# SyNetLEDv2.net
KiCad netlist of a schematic drawn in EAGLE
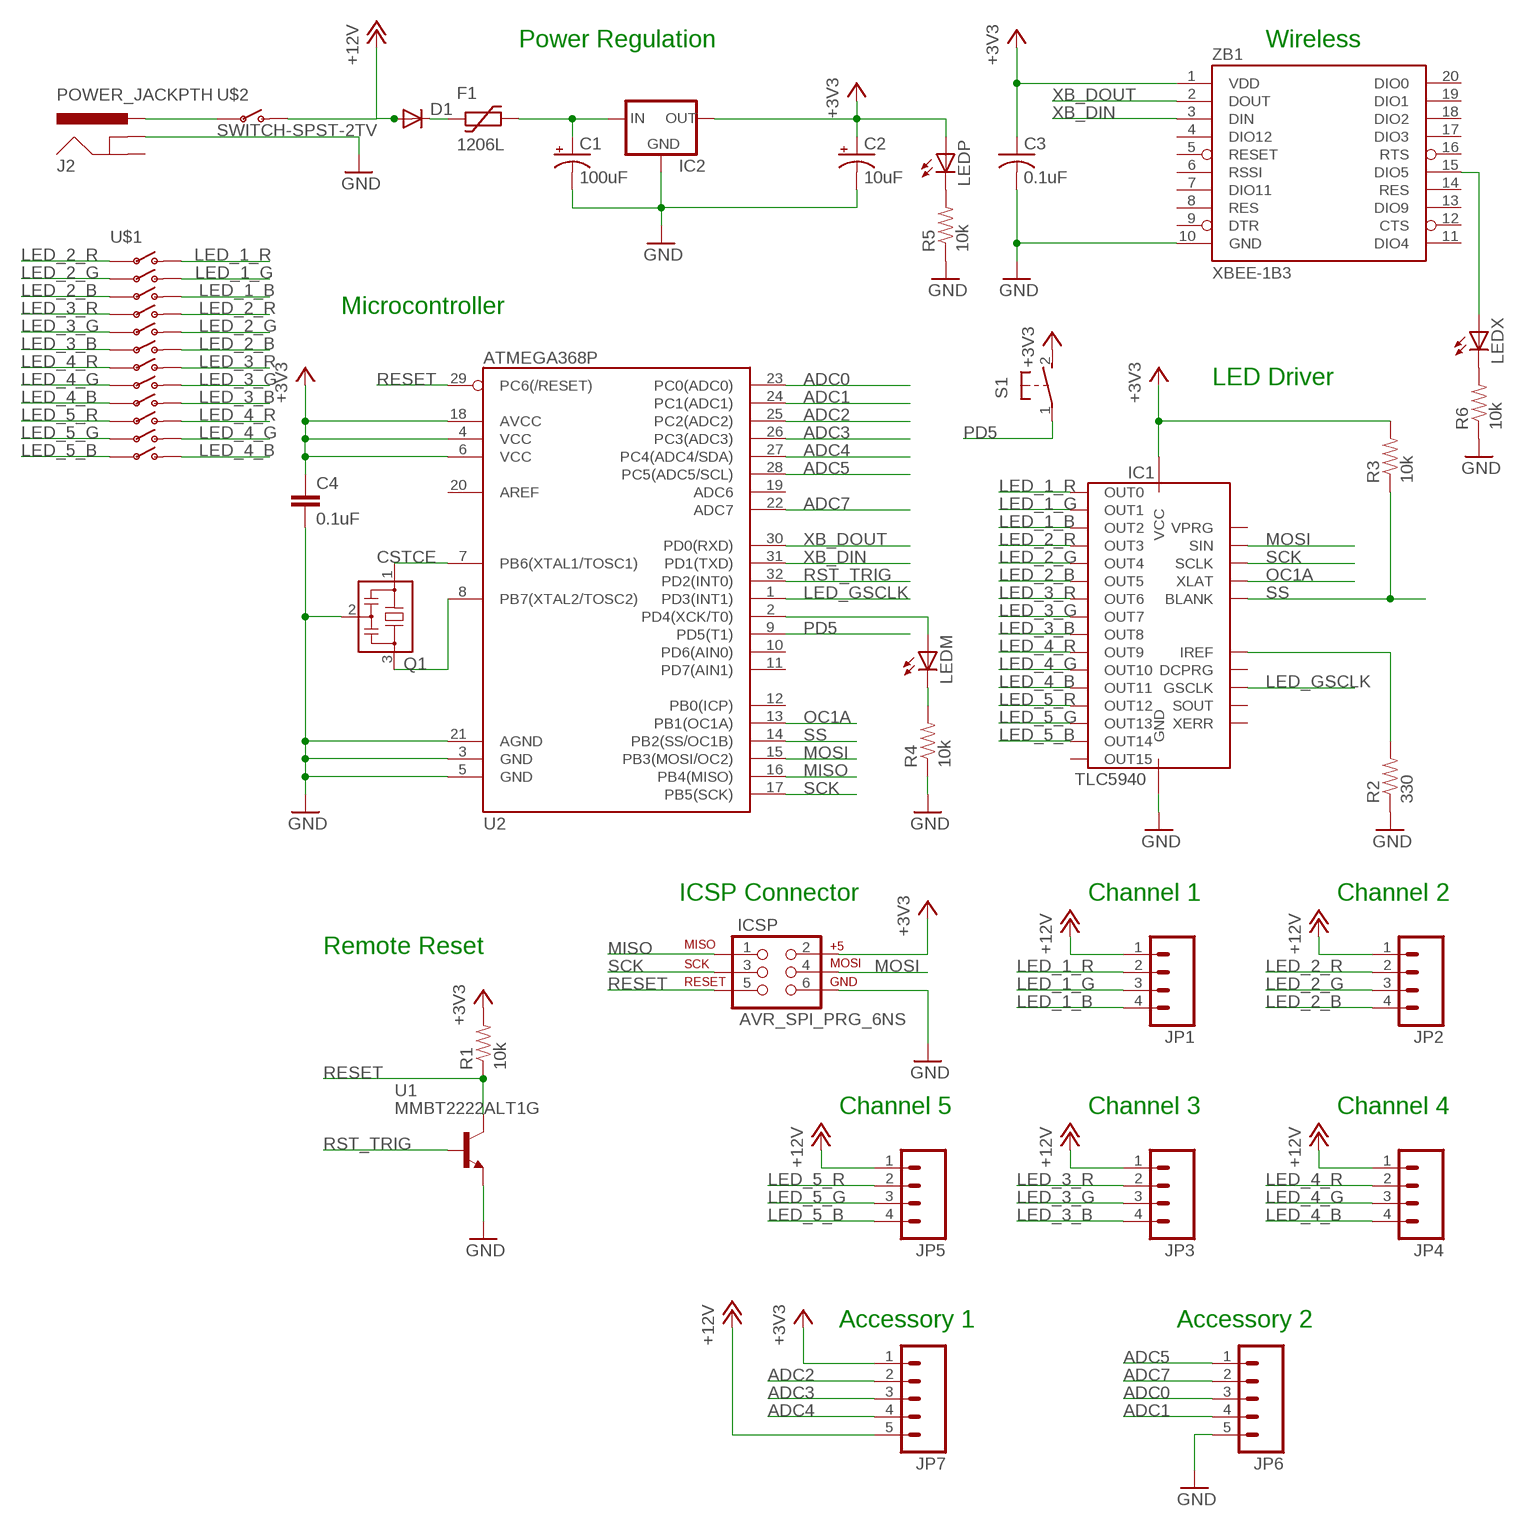
[diagram p0: schematic, sheet 1]

(export (version "E")
  (design (tool "Eeschema 10.0.6"))
  (components
    (comp (ref "C1")
      (value "100uF")
      (footprint "eagle-import:UD-8X10_NICHICON")
      (libsource (lib "eagle-import") (part "CPOL-USUD-8X10"))
    )
    (comp (ref "C2")
      (value "10uF")
      (footprint "eagle-import:UD-4X5,8_NICHICON")
      (libsource (lib "eagle-import") (part "CPOL-USUD-4X5,8"))
    )
    (comp (ref "C3")
      (value "0.1uF")
      (footprint "eagle-import:C1608")
      (libsource (lib "eagle-import") (part "C-USC1608"))
    )
    (comp (ref "C4")
      (value "0.1uF")
      (footprint "eagle-import:0603-CAP")
      (libsource (lib "eagle-import") (part "CAP0603-CAP"))
    )
    (comp (ref "D1")
      (value "DIODESOD")
      (footprint "eagle-import:SOD-323")
      (libsource (lib "eagle-import") (part "DIODESOD"))
    )
    (comp (ref "F1")
      (value "1206L")
      (footprint "eagle-import:1206L")
      (libsource (lib "eagle-import") (part "1206L"))
    )
    (comp (ref "IC1")
      (value "TLC5940")
      (footprint "eagle-import:HTSSOP28PWP")
      (libsource (lib "eagle-import") (part "IC-PACKAGE_DIL28IC_PACKAGE_HTSSOP28PWP"))
    )
    (comp (ref "IC2")
      (value "78LXXSMD")
      (footprint "eagle-import:SOT223")
      (libsource (lib "eagle-import") (part "78LXXSMD"))
    )
    (comp (ref "ICSP")
      (value "AVR_SPI_PRG_6NS")
      (footprint "eagle-import:2X3-NS")
      (libsource (lib "eagle-import") (part "AVR_SPI_PRG_6NS"))
    )
    (comp (ref "J2")
      (value "POWER_JACKPTH")
      (footprint "eagle-import:POWER_JACK_PTH")
      (libsource (lib "eagle-import") (part "POWER_JACKPTH"))
    )
    (comp (ref "JP1")
      (value "M04POLAR")
      (footprint "eagle-import:MOLEX-1X4")
      (libsource (lib "eagle-import") (part "M04POLAR"))
    )
    (comp (ref "JP2")
      (value "M04POLAR")
      (footprint "eagle-import:MOLEX-1X4")
      (libsource (lib "eagle-import") (part "M04POLAR"))
    )
    (comp (ref "JP3")
      (value "M04POLAR")
      (footprint "eagle-import:MOLEX-1X4")
      (libsource (lib "eagle-import") (part "M04POLAR"))
    )
    (comp (ref "JP4")
      (value "M04POLAR")
      (footprint "eagle-import:MOLEX-1X4")
      (libsource (lib "eagle-import") (part "M04POLAR"))
    )
    (comp (ref "JP5")
      (value "M04POLAR")
      (footprint "eagle-import:MOLEX-1X4")
      (libsource (lib "eagle-import") (part "M04POLAR"))
    )
    (comp (ref "JP6")
      (value "M05PTH")
      (footprint "eagle-import:1X05")
      (libsource (lib "eagle-import") (part "M05PTH"))
    )
    (comp (ref "JP7")
      (value "M05PTH")
      (footprint "eagle-import:1X05")
      (libsource (lib "eagle-import") (part "M05PTH"))
    )
    (comp (ref "LEDM")
      (value "LEDSMT-RT")
      (footprint "eagle-import:LED-SMT-RT")
      (libsource (lib "eagle-import") (part "LEDSMT-RT"))
    )
    (comp (ref "LEDP")
      (value "LEDSMT-RT")
      (footprint "eagle-import:LED-SMT-RT")
      (libsource (lib "eagle-import") (part "LEDSMT-RT"))
    )
    (comp (ref "LEDX")
      (value "LEDSMT-RT")
      (footprint "eagle-import:LED-SMT-RT")
      (libsource (lib "eagle-import") (part "LEDSMT-RT"))
    )
    (comp (ref "Q1")
      (value "CSTCE")
      (footprint "eagle-import:CSTCE8")
      (libsource (lib "eagle-import") (part "CSTCE"))
    )
    (comp (ref "R1")
      (value "10k")
      (footprint "eagle-import:0603-RES")
      (libsource (lib "eagle-import") (part "RESISTOR0603-RES"))
    )
    (comp (ref "R2")
      (value "330")
      (footprint "eagle-import:0603-RES")
      (libsource (lib "eagle-import") (part "RESISTOR0603-RES"))
    )
    (comp (ref "R3")
      (value "10k")
      (footprint "eagle-import:0603-RES")
      (libsource (lib "eagle-import") (part "RESISTOR0603-RES"))
    )
    (comp (ref "R4")
      (value "10k")
      (footprint "eagle-import:0603-RES")
      (libsource (lib "eagle-import") (part "RESISTOR0603-RES"))
    )
    (comp (ref "R5")
      (value "10k")
      (footprint "eagle-import:0603-RES")
      (libsource (lib "eagle-import") (part "RESISTOR0603-RES"))
    )
    (comp (ref "R6")
      (value "10k")
      (footprint "eagle-import:0603-RES")
      (libsource (lib "eagle-import") (part "RESISTOR0603-RES"))
    )
    (comp (ref "S1")
      (value "31-XX")
      (footprint "eagle-import:B3F-31XX")
      (fields (field (name "MPN") "B3F-3100"))
      (libsource (lib "eagle-import") (part "31-XX"))
    )
    (comp (ref "U$1")
      (value "DIP12DIP12TH")
      (footprint "eagle-import:DIP12TH")
      (libsource (lib "eagle-import") (part "DIP12DIP12TH"))
    )
    (comp (ref "U$2")
      (value "SWITCH-SPST-2TV")
      (footprint "eagle-import:SWITCH-SPST-VERTICAL")
      (libsource (lib "eagle-import") (part "SWITCH-SPST-2TV"))
    )
    (comp (ref "U1")
      (value "MMBT2222ALT1G")
      (footprint "eagle-import:SOT23")
      (libsource (lib "eagle-import") (part "MMBT2222ALT1G"))
    )
    (comp (ref "U2")
      (value "ATMEGA368P")
      (footprint "eagle-import:TQFP32-08")
      (libsource (lib "eagle-import") (part "ATMEGA368P"))
    )
    (comp (ref "ZB1")
      (value "XBEE-1B3")
      (footprint "eagle-import:XBEE-SMD")
      (libsource (lib "eagle-import") (part "XBEE-1B3"))
    )
  )
  (nets
    (net (code "1") (name "+3V3") (class "Default")
      (node (ref "C2") (pin "+") (pinfunction "+_+") (pintype "passive"))
      (node (ref "C3") (pin "1") (pinfunction "1_1") (pintype "passive"))
      (node (ref "C4") (pin "1") (pinfunction "1_1") (pintype "passive"))
      (node (ref "IC1") (pin "28") (pinfunction "VCC_28") (pintype "power_in"))
      (node (ref "IC2") (pin "3") (pinfunction "OUT_3") (pintype "passive"))
      (node (ref "ICSP") (pin "2") (pinfunction "2_2") (pintype "passive"))
      (node (ref "JP7") (pin "1") (pinfunction "1_1") (pintype "passive"))
      (node (ref "LEDP") (pin "P$1A") (pinfunction "A_P$1A") (pintype "passive"))
      (node (ref "R1") (pin "2") (pinfunction "2_2") (pintype "passive"))
      (node (ref "R3") (pin "2") (pinfunction "2_2") (pintype "passive"))
      (node (ref "S1") (pin "2") (pinfunction "S_2") (pintype "passive"))
      (node (ref "U2") (pin "18") (pinfunction "AVCC_18") (pintype "bidirectional"))
      (node (ref "U2") (pin "4") (pinfunction "VCC_4") (pintype "bidirectional"))
      (node (ref "U2") (pin "6") (pinfunction "VCC_6") (pintype "bidirectional"))
      (node (ref "ZB1") (pin "1") (pinfunction "VDD_1") (pintype "power_in"))
    )
    (net (code "2") (name "+12V") (class "Default")
      (node (ref "D1") (pin "2") (pinfunction "A_2") (pintype "passive"))
      (node (ref "JP1") (pin "1") (pinfunction "1_1") (pintype "passive"))
      (node (ref "JP2") (pin "1") (pinfunction "1_1") (pintype "passive"))
      (node (ref "JP3") (pin "1") (pinfunction "1_1") (pintype "passive"))
      (node (ref "JP4") (pin "1") (pinfunction "1_1") (pintype "passive"))
      (node (ref "JP5") (pin "1") (pinfunction "1_1") (pintype "passive"))
      (node (ref "JP7") (pin "5") (pinfunction "5_5") (pintype "passive"))
      (node (ref "U$2") (pin "1") (pinfunction "O_1") (pintype "passive"))
    )
    (net (code "3") (name "/ADC0") (class "Default")
      (node (ref "JP6") (pin "3") (pinfunction "3_3") (pintype "passive"))
      (node (ref "U2") (pin "23") (pinfunction "PC0(ADC0)_23") (pintype "bidirectional"))
    )
    (net (code "4") (name "/ADC1") (class "Default")
      (node (ref "JP6") (pin "4") (pinfunction "4_4") (pintype "passive"))
      (node (ref "U2") (pin "24") (pinfunction "PC1(ADC1)_24") (pintype "bidirectional"))
    )
    (net (code "5") (name "/ADC2") (class "Default")
      (node (ref "JP7") (pin "2") (pinfunction "2_2") (pintype "passive"))
      (node (ref "U2") (pin "25") (pinfunction "PC2(ADC2)_25") (pintype "bidirectional"))
    )
    (net (code "6") (name "/ADC3") (class "Default")
      (node (ref "JP7") (pin "3") (pinfunction "3_3") (pintype "passive"))
      (node (ref "U2") (pin "26") (pinfunction "PC3(ADC3)_26") (pintype "bidirectional"))
    )
    (net (code "7") (name "/ADC4") (class "Default")
      (node (ref "JP7") (pin "4") (pinfunction "4_4") (pintype "passive"))
      (node (ref "U2") (pin "27") (pinfunction "PC4(ADC4/SDA)_27") (pintype "bidirectional"))
    )
    (net (code "8") (name "/ADC5") (class "Default")
      (node (ref "JP6") (pin "1") (pinfunction "1_1") (pintype "passive"))
      (node (ref "U2") (pin "28") (pinfunction "PC5(ADC5/SCL)_28") (pintype "bidirectional"))
    )
    (net (code "9") (name "/ADC7") (class "Default")
      (node (ref "JP6") (pin "2") (pinfunction "2_2") (pintype "passive"))
      (node (ref "U2") (pin "22") (pinfunction "ADC7_22") (pintype "bidirectional"))
    )
    (net (code "10") (name "/LED_1_B") (class "Default")
      (node (ref "IC1") (pin "9") (pinfunction "OUT2_9") (pintype "open_collector"))
      (node (ref "JP1") (pin "4") (pinfunction "4_4") (pintype "passive"))
      (node (ref "U$1") (pin "P$3") (pinfunction "P3B_P$3") (pintype "passive"))
    )
    (net (code "11") (name "/LED_1_G") (class "Default")
      (node (ref "IC1") (pin "8") (pinfunction "OUT1_8") (pintype "open_collector"))
      (node (ref "JP1") (pin "3") (pinfunction "3_3") (pintype "passive"))
      (node (ref "U$1") (pin "P$2") (pinfunction "P2B_P$2") (pintype "passive"))
    )
    (net (code "12") (name "/LED_1_R") (class "Default")
      (node (ref "IC1") (pin "7") (pinfunction "OUT0_7") (pintype "open_collector"))
      (node (ref "JP1") (pin "2") (pinfunction "2_2") (pintype "passive"))
      (node (ref "U$1") (pin "P$1") (pinfunction "P1B_P$1") (pintype "passive"))
    )
    (net (code "13") (name "/LED_2_B") (class "Default")
      (node (ref "IC1") (pin "12") (pinfunction "OUT5_12") (pintype "open_collector"))
      (node (ref "JP2") (pin "4") (pinfunction "4_4") (pintype "passive"))
      (node (ref "U$1") (pin "O$3") (pinfunction "P3A_O$3") (pintype "passive"))
      (node (ref "U$1") (pin "P$6") (pinfunction "P6B_P$6") (pintype "passive"))
    )
    (net (code "14") (name "/LED_2_G") (class "Default")
      (node (ref "IC1") (pin "11") (pinfunction "OUT4_11") (pintype "open_collector"))
      (node (ref "JP2") (pin "3") (pinfunction "3_3") (pintype "passive"))
      (node (ref "U$1") (pin "O$2") (pinfunction "P2A_O$2") (pintype "passive"))
      (node (ref "U$1") (pin "P$5") (pinfunction "P5B_P$5") (pintype "passive"))
    )
    (net (code "15") (name "/LED_2_R") (class "Default")
      (node (ref "IC1") (pin "10") (pinfunction "OUT3_10") (pintype "open_collector"))
      (node (ref "JP2") (pin "2") (pinfunction "2_2") (pintype "passive"))
      (node (ref "U$1") (pin "O$1") (pinfunction "P1A_O$1") (pintype "passive"))
      (node (ref "U$1") (pin "P$4") (pinfunction "P4B_P$4") (pintype "passive"))
    )
    (net (code "16") (name "/LED_3_B") (class "Default")
      (node (ref "IC1") (pin "15") (pinfunction "OUT8_15") (pintype "open_collector"))
      (node (ref "JP3") (pin "4") (pinfunction "4_4") (pintype "passive"))
      (node (ref "U$1") (pin "O$6") (pinfunction "P6A_O$6") (pintype "passive"))
      (node (ref "U$1") (pin "P$9") (pinfunction "P9B_P$9") (pintype "passive"))
    )
    (net (code "17") (name "/LED_3_G") (class "Default")
      (node (ref "IC1") (pin "14") (pinfunction "OUT7_14") (pintype "open_collector"))
      (node (ref "JP3") (pin "3") (pinfunction "3_3") (pintype "passive"))
      (node (ref "U$1") (pin "O$5") (pinfunction "P5A_O$5") (pintype "passive"))
      (node (ref "U$1") (pin "P$8") (pinfunction "P8B_P$8") (pintype "passive"))
    )
    (net (code "18") (name "/LED_3_R") (class "Default")
      (node (ref "IC1") (pin "13") (pinfunction "OUT6_13") (pintype "open_collector"))
      (node (ref "JP3") (pin "2") (pinfunction "2_2") (pintype "passive"))
      (node (ref "U$1") (pin "O$4") (pinfunction "P4A_O$4") (pintype "passive"))
      (node (ref "U$1") (pin "P$7") (pinfunction "P7B_P$7") (pintype "passive"))
    )
    (net (code "19") (name "/LED_4_B") (class "Default")
      (node (ref "IC1") (pin "18") (pinfunction "OUT11_18") (pintype "open_collector"))
      (node (ref "JP4") (pin "4") (pinfunction "4_4") (pintype "passive"))
      (node (ref "U$1") (pin "O$9") (pinfunction "P9A_O$9") (pintype "passive"))
      (node (ref "U$1") (pin "P$12") (pinfunction "P12B_P$12") (pintype "passive"))
    )
    (net (code "20") (name "/LED_4_G") (class "Default")
      (node (ref "IC1") (pin "17") (pinfunction "OUT10_17") (pintype "open_collector"))
      (node (ref "JP4") (pin "3") (pinfunction "3_3") (pintype "passive"))
      (node (ref "U$1") (pin "O$8") (pinfunction "P8A_O$8") (pintype "passive"))
      (node (ref "U$1") (pin "P$11") (pinfunction "P11B_P$11") (pintype "passive"))
    )
    (net (code "21") (name "/LED_4_R") (class "Default")
      (node (ref "IC1") (pin "16") (pinfunction "OUT9_16") (pintype "open_collector"))
      (node (ref "JP4") (pin "2") (pinfunction "2_2") (pintype "passive"))
      (node (ref "U$1") (pin "O$7") (pinfunction "P7A_O$7") (pintype "passive"))
      (node (ref "U$1") (pin "P$10") (pinfunction "P10B_P$10") (pintype "passive"))
    )
    (net (code "22") (name "/LED_5_B") (class "Default")
      (node (ref "IC1") (pin "21") (pinfunction "OUT14_21") (pintype "open_collector"))
      (node (ref "JP5") (pin "4") (pinfunction "4_4") (pintype "passive"))
      (node (ref "U$1") (pin "O$12") (pinfunction "P12A_O$12") (pintype "passive"))
    )
    (net (code "23") (name "/LED_5_G") (class "Default")
      (node (ref "IC1") (pin "20") (pinfunction "OUT13_20") (pintype "open_collector"))
      (node (ref "JP5") (pin "3") (pinfunction "3_3") (pintype "passive"))
      (node (ref "U$1") (pin "O$11") (pinfunction "P11A_O$11") (pintype "passive"))
    )
    (net (code "24") (name "/LED_5_R") (class "Default")
      (node (ref "IC1") (pin "19") (pinfunction "OUT12_19") (pintype "open_collector"))
      (node (ref "JP5") (pin "2") (pinfunction "2_2") (pintype "passive"))
      (node (ref "U$1") (pin "O$10") (pinfunction "P10A_O$10") (pintype "passive"))
    )
    (net (code "25") (name "/LED_GSCLK") (class "Default")
      (node (ref "IC1") (pin "25") (pinfunction "GSCLK_25") (pintype "input"))
      (node (ref "U2") (pin "1") (pinfunction "PD3(INT1)_1") (pintype "bidirectional"))
    )
    (net (code "26") (name "/MISO") (class "Default")
      (node (ref "ICSP") (pin "1") (pinfunction "1_1") (pintype "passive"))
      (node (ref "U2") (pin "16") (pinfunction "PB4(MISO)_16") (pintype "bidirectional"))
    )
    (net (code "27") (name "/MOSI") (class "Default")
      (node (ref "IC1") (pin "5") (pinfunction "SIN_5") (pintype "input"))
      (node (ref "ICSP") (pin "4") (pinfunction "4_4") (pintype "passive"))
      (node (ref "U2") (pin "15") (pinfunction "PB3(MOSI/OC2)_15") (pintype "bidirectional"))
    )
    (net (code "28") (name "/OC1A") (class "Default")
      (node (ref "IC1") (pin "3") (pinfunction "XLAT_3") (pintype "input"))
      (node (ref "U2") (pin "13") (pinfunction "PB1(OC1A)_13") (pintype "bidirectional"))
    )
    (net (code "29") (name "/PD5") (class "Default")
      (node (ref "S1") (pin "1") (pinfunction "P_1") (pintype "passive"))
      (node (ref "U2") (pin "9") (pinfunction "PD5(T1)_9") (pintype "bidirectional"))
    )
    (net (code "30") (name "/RESET") (class "Default")
      (node (ref "ICSP") (pin "5") (pinfunction "5_5") (pintype "passive"))
      (node (ref "R1") (pin "1") (pinfunction "1_1") (pintype "passive"))
      (node (ref "U1") (pin "3") (pinfunction "C_3") (pintype "passive"))
      (node (ref "U2") (pin "29") (pinfunction "PC6(/RESET)_29") (pintype "bidirectional"))
    )
    (net (code "31") (name "/RST_TRIG") (class "Default")
      (node (ref "U1") (pin "1") (pinfunction "B_1") (pintype "passive"))
      (node (ref "U2") (pin "32") (pinfunction "PD2(INT0)_32") (pintype "bidirectional"))
    )
    (net (code "32") (name "/SCK") (class "Default")
      (node (ref "IC1") (pin "4") (pinfunction "SCLK_4") (pintype "input"))
      (node (ref "ICSP") (pin "3") (pinfunction "3_3") (pintype "passive"))
      (node (ref "U2") (pin "17") (pinfunction "PB5(SCK)_17") (pintype "bidirectional"))
    )
    (net (code "33") (name "/SS") (class "Default")
      (node (ref "IC1") (pin "2") (pinfunction "BLANK_2") (pintype "input"))
      (node (ref "R3") (pin "1") (pinfunction "1_1") (pintype "passive"))
      (node (ref "U2") (pin "14") (pinfunction "PB2(SS/OC1B)_14") (pintype "bidirectional"))
    )
    (net (code "34") (name "/XB_DIN") (class "Default")
      (node (ref "U2") (pin "31") (pinfunction "PD1(TXD)_31") (pintype "bidirectional"))
      (node (ref "ZB1") (pin "3") (pinfunction "DIN_3") (pintype "input"))
    )
    (net (code "35") (name "/XB_DOUT") (class "Default")
      (node (ref "U2") (pin "30") (pinfunction "PD0(RXD)_30") (pintype "bidirectional"))
      (node (ref "ZB1") (pin "2") (pinfunction "DOUT_2") (pintype "output"))
    )
    (net (code "36") (name "GND") (class "Default")
      (node (ref "C1") (pin "-") (pinfunction "-_-") (pintype "passive"))
      (node (ref "C2") (pin "-") (pinfunction "-_-") (pintype "passive"))
      (node (ref "C3") (pin "2") (pinfunction "2_2") (pintype "passive"))
      (node (ref "C4") (pin "2") (pinfunction "2_2") (pintype "passive"))
      (node (ref "IC1") (pin "1") (pinfunction "GND_1") (pintype "power_in"))
      (node (ref "IC2") (pin "2") (pinfunction "GND_2") (pintype "input"))
      (node (ref "IC2") (pin "4") (pinfunction "GND_4") (pintype "input"))
      (node (ref "ICSP") (pin "6") (pinfunction "6_6") (pintype "passive"))
      (node (ref "J2") (pin "GNDBREAK") (pinfunction "GNDBREAK_GNDBREAK") (pintype "bidirectional"))
      (node (ref "JP6") (pin "5") (pinfunction "5_5") (pintype "passive"))
      (node (ref "Q1") (pin "2") (pinfunction "2_2") (pintype "passive"))
      (node (ref "R2") (pin "1") (pinfunction "1_1") (pintype "passive"))
      (node (ref "R4") (pin "1") (pinfunction "1_1") (pintype "passive"))
      (node (ref "R5") (pin "1") (pinfunction "1_1") (pintype "passive"))
      (node (ref "R6") (pin "1") (pinfunction "1_1") (pintype "passive"))
      (node (ref "U1") (pin "2") (pinfunction "E_2") (pintype "passive"))
      (node (ref "U2") (pin "21") (pinfunction "AGND_21") (pintype "bidirectional"))
      (node (ref "U2") (pin "3") (pinfunction "GND_3") (pintype "bidirectional"))
      (node (ref "U2") (pin "5") (pinfunction "GND_5") (pintype "bidirectional"))
      (node (ref "ZB1") (pin "10") (pinfunction "GND_10") (pintype "power_in"))
    )
    (net (code "37") (name "Net-(D1-C)") (class "Default")
      (node (ref "D1") (pin "1") (pinfunction "C_1") (pintype "passive"))
      (node (ref "F1") (pin "P$1") (pinfunction "1_P$1") (pintype "passive"))
    )
    (net (code "38") (name "Net-(F1-2)") (class "Default")
      (node (ref "C1") (pin "+") (pinfunction "+_+") (pintype "passive"))
      (node (ref "F1") (pin "P$2") (pinfunction "2_P$2") (pintype "passive"))
      (node (ref "IC2") (pin "1") (pinfunction "IN_1") (pintype "input"))
    )
    (net (code "39") (name "Net-(IC1-IREF)") (class "Default")
      (node (ref "IC1") (pin "27") (pinfunction "IREF_27") (pintype "passive"))
      (node (ref "R2") (pin "2") (pinfunction "2_2") (pintype "passive"))
    )
    (net (code "40") (name "Net-(LEDM-A)") (class "Default")
      (node (ref "LEDM") (pin "P$1A") (pinfunction "A_P$1A") (pintype "passive"))
      (node (ref "U2") (pin "2") (pinfunction "PD4(XCK/T0)_2") (pintype "bidirectional"))
    )
    (net (code "41") (name "Net-(LEDM-C)") (class "Default")
      (node (ref "LEDM") (pin "P$2C") (pinfunction "C_P$2C") (pintype "passive"))
      (node (ref "R4") (pin "2") (pinfunction "2_2") (pintype "passive"))
    )
    (net (code "42") (name "Net-(LEDP-C)") (class "Default")
      (node (ref "LEDP") (pin "P$2C") (pinfunction "C_P$2C") (pintype "passive"))
      (node (ref "R5") (pin "2") (pinfunction "2_2") (pintype "passive"))
    )
    (net (code "43") (name "Net-(LEDX-A)") (class "Default")
      (node (ref "LEDX") (pin "P$1A") (pinfunction "A_P$1A") (pintype "passive"))
      (node (ref "ZB1") (pin "15") (pinfunction "DIO5_15") (pintype "bidirectional"))
    )
    (net (code "44") (name "Net-(LEDX-C)") (class "Default")
      (node (ref "LEDX") (pin "P$2C") (pinfunction "C_P$2C") (pintype "passive"))
      (node (ref "R6") (pin "2") (pinfunction "2_2") (pintype "passive"))
    )
    (net (code "45") (name "Net-(U$2-P)") (class "Default")
      (node (ref "J2") (pin "PWR") (pinfunction "PWR_PWR") (pintype "bidirectional"))
      (node (ref "U$2") (pin "2") (pinfunction "P_2") (pintype "passive"))
    )
    (net (code "46") (name "Net-(U2-PB6(XTAL1{slash}TOSC1))") (class "Default")
      (node (ref "Q1") (pin "1") (pinfunction "1_1") (pintype "passive"))
      (node (ref "U2") (pin "7") (pinfunction "PB6(XTAL1/TOSC1)_7") (pintype "bidirectional"))
    )
    (net (code "47") (name "Net-(U2-PB7(XTAL2{slash}TOSC2))") (class "Default")
      (node (ref "Q1") (pin "3") (pinfunction "3_3") (pintype "passive"))
      (node (ref "U2") (pin "8") (pinfunction "PB7(XTAL2/TOSC2)_8") (pintype "bidirectional"))
    )
    (net (code "48") (name "unconnected-(IC1-DCPRG-Pad26)") (class "Default")
      (node (ref "IC1") (pin "26") (pinfunction "DCPRG_26") (pintype "input"))
    )
    (net (code "49") (name "unconnected-(IC1-OUT15-Pad22)") (class "Default")
      (node (ref "IC1") (pin "22") (pinfunction "OUT15_22") (pintype "open_collector"))
    )
    (net (code "50") (name "unconnected-(IC1-SOUT-Pad24)") (class "Default")
      (node (ref "IC1") (pin "24") (pinfunction "SOUT_24") (pintype "output"))
    )
    (net (code "51") (name "unconnected-(IC1-VPRG-Pad6)") (class "Default")
      (node (ref "IC1") (pin "6") (pinfunction "VPRG_6") (pintype "input"))
    )
    (net (code "52") (name "unconnected-(IC1-XERR-Pad23)") (class "Default")
      (node (ref "IC1") (pin "23") (pinfunction "XERR_23") (pintype "open_collector"))
    )
    (net (code "53") (name "unconnected-(J2-PadGND)") (class "Default")
      (node (ref "J2") (pin "GND") (pinfunction "GND_GND") (pintype "bidirectional"))
    )
    (net (code "54") (name "unconnected-(U2-ADC6-Pad19)") (class "Default")
      (node (ref "U2") (pin "19") (pinfunction "ADC6_19") (pintype "bidirectional"))
    )
    (net (code "55") (name "unconnected-(U2-AREF-Pad20)") (class "Default")
      (node (ref "U2") (pin "20") (pinfunction "AREF_20") (pintype "bidirectional"))
    )
    (net (code "56") (name "unconnected-(U2-PB0(ICP)-Pad12)") (class "Default")
      (node (ref "U2") (pin "12") (pinfunction "PB0(ICP)_12") (pintype "bidirectional"))
    )
    (net (code "57") (name "unconnected-(U2-PD6(AIN0)-Pad10)") (class "Default")
      (node (ref "U2") (pin "10") (pinfunction "PD6(AIN0)_10") (pintype "bidirectional"))
    )
    (net (code "58") (name "unconnected-(U2-PD7(AIN1)-Pad11)") (class "Default")
      (node (ref "U2") (pin "11") (pinfunction "PD7(AIN1)_11") (pintype "bidirectional"))
    )
    (net (code "59") (name "unconnected-(ZB1-CTS-Pad12)") (class "Default")
      (node (ref "ZB1") (pin "12") (pinfunction "CTS_12") (pintype "output"))
    )
    (net (code "60") (name "unconnected-(ZB1-DIO0-Pad20)") (class "Default")
      (node (ref "ZB1") (pin "20") (pinfunction "DIO0_20") (pintype "bidirectional"))
    )
    (net (code "61") (name "unconnected-(ZB1-DIO1-Pad19)") (class "Default")
      (node (ref "ZB1") (pin "19") (pinfunction "DIO1_19") (pintype "bidirectional"))
    )
    (net (code "62") (name "unconnected-(ZB1-DIO2-Pad18)") (class "Default")
      (node (ref "ZB1") (pin "18") (pinfunction "DIO2_18") (pintype "bidirectional"))
    )
    (net (code "63") (name "unconnected-(ZB1-DIO3-Pad17)") (class "Default")
      (node (ref "ZB1") (pin "17") (pinfunction "DIO3_17") (pintype "bidirectional"))
    )
    (net (code "64") (name "unconnected-(ZB1-DIO4-Pad11)") (class "Default")
      (node (ref "ZB1") (pin "11") (pinfunction "DIO4_11") (pintype "bidirectional"))
    )
    (net (code "65") (name "unconnected-(ZB1-DIO9-Pad13)") (class "Default")
      (node (ref "ZB1") (pin "13") (pinfunction "DIO9_13") (pintype "bidirectional"))
    )
    (net (code "66") (name "unconnected-(ZB1-DIO11-Pad7)") (class "Default")
      (node (ref "ZB1") (pin "7") (pinfunction "DIO11_7") (pintype "bidirectional"))
    )
    (net (code "67") (name "unconnected-(ZB1-DIO12-Pad4)") (class "Default")
      (node (ref "ZB1") (pin "4") (pinfunction "DIO12_4") (pintype "bidirectional"))
    )
    (net (code "68") (name "unconnected-(ZB1-DTR-Pad9)") (class "Default")
      (node (ref "ZB1") (pin "9") (pinfunction "DTR_9") (pintype "bidirectional"))
    )
    (net (code "69") (name "unconnected-(ZB1-RES-Pad8)") (class "Default")
      (node (ref "ZB1") (pin "8") (pinfunction "RES_8") (pintype "bidirectional"))
    )
    (net (code "70") (name "unconnected-(ZB1-RES-Pad14)") (class "Default")
      (node (ref "ZB1") (pin "14") (pinfunction "RES_14") (pintype "bidirectional"))
    )
    (net (code "71") (name "unconnected-(ZB1-RESET-Pad5)") (class "Default")
      (node (ref "ZB1") (pin "5") (pinfunction "RESET_5") (pintype "input"))
    )
    (net (code "72") (name "unconnected-(ZB1-RSSI-Pad6)") (class "Default")
      (node (ref "ZB1") (pin "6") (pinfunction "RSSI_6") (pintype "bidirectional"))
    )
    (net (code "73") (name "unconnected-(ZB1-RTS-Pad16)") (class "Default")
      (node (ref "ZB1") (pin "16") (pinfunction "RTS_16") (pintype "input"))
    )
  )
)
